# buzzer.net
KiCad netlist of a schematic drawn in EAGLE
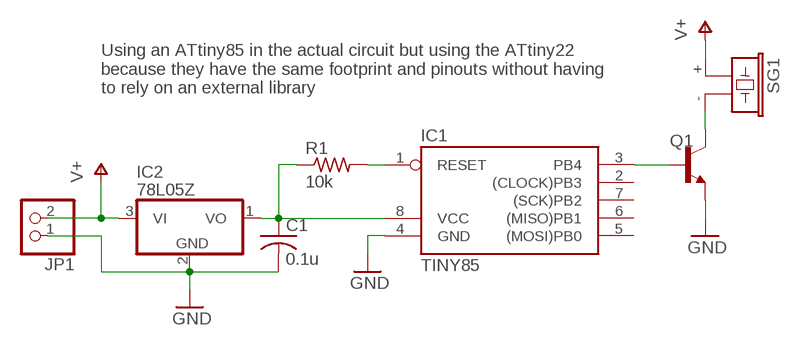
[diagram p0: schematic, sheet 1]

(export (version "E")
  (design (tool "Eeschema 10.0.6"))
  (components
    (comp (ref "C1")
      (value "0.1u")
      (footprint "eagle-import:C0402")
      (libsource (lib "eagle-import") (part "C-USC0402"))
    )
    (comp (ref "IC1")
      (value "TINY85")
      (footprint "eagle-import:DIL08")
      (libsource (lib "eagle-import") (part "TINY22P"))
    )
    (comp (ref "IC2")
      (value "78L05Z")
      (footprint "eagle-import:TO92")
      (libsource (lib "eagle-import") (part "78ZL05"))
    )
    (comp (ref "JP1")
      (value "PINHD-1X2")
      (footprint "eagle-import:1X02")
      (libsource (lib "eagle-import") (part "PINHD-1X2"))
    )
    (comp (ref "Q1")
      (value "BCX70SMD")
      (footprint "eagle-import:SOT23")
      (libsource (lib "eagle-import") (part "BCX70SMD"))
    )
    (comp (ref "R1")
      (value "10k")
      (footprint "eagle-import:R0402")
      (libsource (lib "eagle-import") (part "R-US_R0402"))
    )
    (comp (ref "SG1")
      (value "F/CM12P")
      (footprint "eagle-import:F_CM12P")
      (libsource (lib "eagle-import") (part "F/CM12P"))
    )
  )
  (nets
    (net (code "1") (name "GND") (class "Default")
      (node (ref "C1") (pin "2") (pinfunction "2_2") (pintype "passive"))
      (node (ref "IC1") (pin "4") (pinfunction "GND_4") (pintype "power_in"))
      (node (ref "IC2") (pin "2") (pinfunction "GND_2") (pintype "passive"))
      (node (ref "JP1") (pin "1") (pinfunction "1_1") (pintype "passive"))
      (node (ref "Q1") (pin "2") (pinfunction "E_2") (pintype "passive"))
    )
    (net (code "2") (name "Net-(IC1-PB4)") (class "Default")
      (node (ref "IC1") (pin "3") (pinfunction "PB4_3") (pintype "bidirectional"))
      (node (ref "Q1") (pin "1") (pinfunction "B_1") (pintype "passive"))
    )
    (net (code "3") (name "Net-(IC1-RESET)") (class "Default")
      (node (ref "IC1") (pin "1") (pinfunction "RESET_1") (pintype "input"))
      (node (ref "R1") (pin "2") (pinfunction "2_2") (pintype "passive"))
    )
    (net (code "4") (name "Net-(IC1-VCC)") (class "Default")
      (node (ref "C1") (pin "1") (pinfunction "1_1") (pintype "passive"))
      (node (ref "IC1") (pin "8") (pinfunction "VCC_8") (pintype "power_in"))
      (node (ref "IC2") (pin "1") (pinfunction "VO_1") (pintype "passive"))
      (node (ref "R1") (pin "1") (pinfunction "1_1") (pintype "passive"))
    )
    (net (code "5") (name "Net-(Q1-C)") (class "Default")
      (node (ref "Q1") (pin "3") (pinfunction "C_3") (pintype "passive"))
      (node (ref "SG1") (pin "-") (pinfunction "2_-") (pintype "passive"))
    )
    (net (code "6") (name "V+") (class "Default")
      (node (ref "IC2") (pin "3") (pinfunction "VI_3") (pintype "input"))
      (node (ref "JP1") (pin "2") (pinfunction "2_2") (pintype "passive"))
      (node (ref "SG1") (pin "+") (pinfunction "1_+") (pintype "passive"))
    )
    (net (code "7") (name "unconnected-(IC1-(CLOCK)PB3-Pad2)") (class "Default")
      (node (ref "IC1") (pin "2") (pinfunction "(CLOCK)PB3_2") (pintype "bidirectional"))
    )
    (net (code "8") (name "unconnected-(IC1-(MISO)PB1-Pad6)") (class "Default")
      (node (ref "IC1") (pin "6") (pinfunction "(MISO)PB1_6") (pintype "bidirectional"))
    )
    (net (code "9") (name "unconnected-(IC1-(MOSI)PB0-Pad5)") (class "Default")
      (node (ref "IC1") (pin "5") (pinfunction "(MOSI)PB0_5") (pintype "bidirectional"))
    )
    (net (code "10") (name "unconnected-(IC1-(SCK)PB2-Pad7)") (class "Default")
      (node (ref "IC1") (pin "7") (pinfunction "(SCK)PB2_7") (pintype "bidirectional"))
    )
  )
)
